# LCDTFT_FPC40P_SPI.net
KiCad netlist of a schematic drawn in Altium Designer
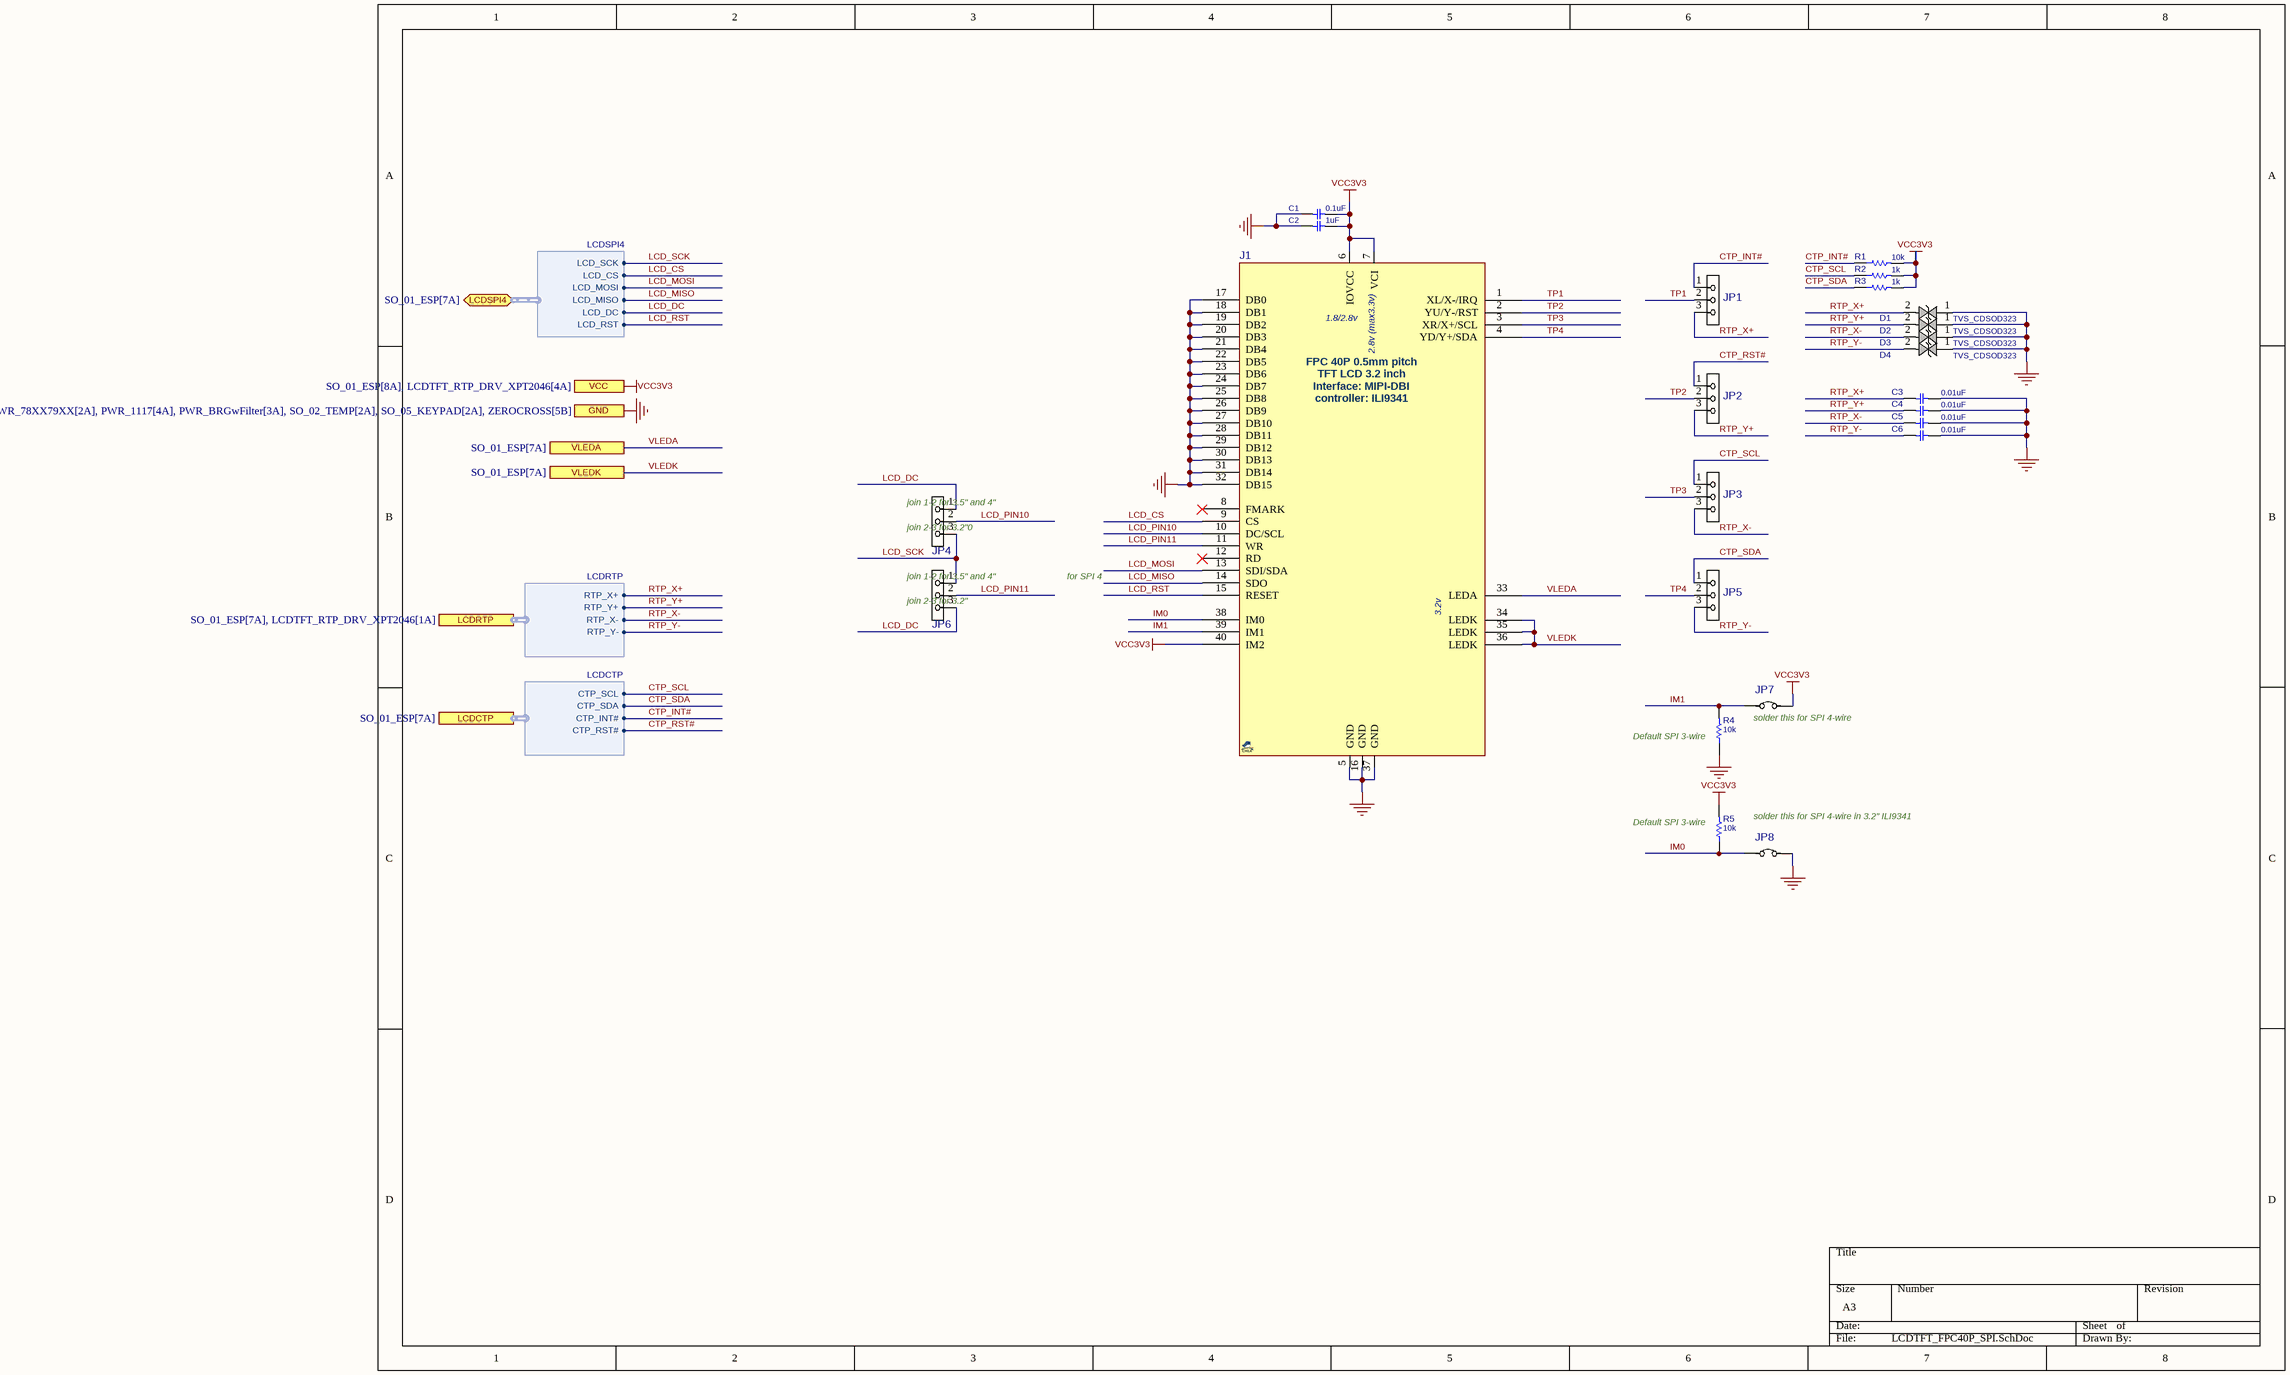
[diagram p0: LCDTFT_FPC40P_SPI.SchDoc]

(export (version "E")
  (design (tool "Eeschema 10.0.6"))
  (components
    (comp (ref "C1")
      (value "0.1uF")
      (footprint "C0402")
      (description "CAP, MLCC")
      (fields (field (name "MANF_P#") "GRM155R71H104KE14D") (field (name "MANF") "Murata"))
      (libsource (lib "passive_smd") (part "CAP_SMD_MLCC"))
    )
    (comp (ref "C2")
      (value "1uF")
      (footprint "C0402")
      (description "CAP, MLCC")
      (libsource (lib "passive_smd") (part "CAP_SMD_MLCC"))
    )
    (comp (ref "C3")
      (value "0.01uF")
      (footprint "C0402")
      (description "CAP, MLCC")
      (libsource (lib "passive_smd") (part "CAP_SMD_MLCC"))
    )
    (comp (ref "C4")
      (value "0.01uF")
      (footprint "C0402")
      (description "CAP, MLCC")
      (libsource (lib "passive_smd") (part "CAP_SMD_MLCC"))
    )
    (comp (ref "C5")
      (value "0.01uF")
      (footprint "C0402")
      (description "CAP, MLCC")
      (libsource (lib "passive_smd") (part "CAP_SMD_MLCC"))
    )
    (comp (ref "C6")
      (value "0.01uF")
      (footprint "C0402")
      (description "CAP, MLCC")
      (libsource (lib "passive_smd") (part "CAP_SMD_MLCC"))
    )
    (comp (ref "D1")
      (value "TVS_CDSOD323")
      (footprint "D0805")
      (description "TVS, ESD PROTECT, Bidirectional")
      (fields (field (name "MANF_P#") "CDSOD323-T12C") (field (name "MANF") "Bourns"))
      (libsource (lib "protect_tvs_esd_fuse") (part "TVS_CDSOD323"))
    )
    (comp (ref "D2")
      (value "TVS_CDSOD323")
      (footprint "D0805")
      (description "TVS, ESD PROTECT, Bidirectional")
      (fields (field (name "MANF_P#") "CDSOD323-T12C") (field (name "MANF") "Bourns"))
      (libsource (lib "protect_tvs_esd_fuse") (part "TVS_CDSOD323"))
    )
    (comp (ref "D3")
      (value "TVS_CDSOD323")
      (footprint "D0805")
      (description "TVS, ESD PROTECT, Bidirectional")
      (fields (field (name "MANF_P#") "CDSOD323-T12C") (field (name "MANF") "Bourns"))
      (libsource (lib "protect_tvs_esd_fuse") (part "TVS_CDSOD323"))
    )
    (comp (ref "D4")
      (value "TVS_CDSOD323")
      (footprint "D0805")
      (description "TVS, ESD PROTECT, Bidirectional")
      (fields (field (name "MANF_P#") "CDSOD323-T12C") (field (name "MANF") "Bourns"))
      (libsource (lib "protect_tvs_esd_fuse") (part "TVS_CDSOD323"))
    )
    (comp (ref "J1")
      (value "FPC50_40")
      (footprint "FPC50_40T")
      (description "LCD TFT Color, FPC40P, 3.2\" with touch")
      (fields (field (name "MANF") "Hirose") (field (name "MANF_P#") "FH12A-40S-0.5SH"))
      (libsource (lib "lcdtft") (part "LCDTFT_DBI_FPC40P_3.2INCH"))
    )
    (comp (ref "JP1")
      (value "JMPHDR3PIN")
      (footprint "JP_3_60W")
      (description "JUMPER, HEADER 3PIN")
      (fields (field (name "MANF") "MANF") (field (name "MANF_P#") "MANF_P#"))
      (libsource (lib "") (part "JUMPER_SOLDER_3P_1"))
    )
    (comp (ref "JP2")
      (value "JMPHDR3PIN")
      (footprint "JP_3_60W")
      (description "JUMPER, HEADER 3PIN")
      (fields (field (name "MANF") "MANF") (field (name "MANF_P#") "MANF_P#"))
      (libsource (lib "") (part "JUMPER_SOLDER_3P_1"))
    )
    (comp (ref "JP3")
      (value "JMPHDR3PIN")
      (footprint "JP_3_60W")
      (description "JUMPER, HEADER 3PIN")
      (fields (field (name "MANF") "MANF") (field (name "MANF_P#") "MANF_P#"))
      (libsource (lib "") (part "JUMPER_SOLDER_3P_1"))
    )
    (comp (ref "JP4")
      (value "JMPHDR3PIN")
      (footprint "JP_3_60W")
      (description "JUMPER, HEADER 3PIN")
      (fields (field (name "MANF") "MANF") (field (name "MANF_P#") "MANF_P#"))
      (libsource (lib "test-tp_jumper") (part "JUMPER_SOLDER_3P"))
    )
    (comp (ref "JP5")
      (value "JMPHDR3PIN")
      (footprint "JP_3_60W")
      (description "JUMPER, HEADER 3PIN")
      (fields (field (name "MANF") "MANF") (field (name "MANF_P#") "MANF_P#"))
      (libsource (lib "") (part "JUMPER_SOLDER_3P_1"))
    )
    (comp (ref "JP6")
      (value "JMPHDR3PIN")
      (footprint "JP_3_60W")
      (description "JUMPER, HEADER 3PIN")
      (fields (field (name "MANF") "MANF") (field (name "MANF_P#") "MANF_P#"))
      (libsource (lib "test-tp_jumper") (part "JUMPER_SOLDER_3P"))
    )
    (comp (ref "JP7")
      (value "JMPSOLDER")
      (footprint "JP_60X100")
      (description "JUMPER, HEADER 2PIN")
      (fields (field (name "MANF") "MANF") (field (name "MANF_P#") "MANF_P#"))
      (libsource (lib "test-tp_jumper") (part "JUMPER_SOLDER"))
    )
    (comp (ref "JP8")
      (value "JMPSOLDER")
      (footprint "JP_60X100")
      (description "JUMPER, HEADER 2PIN")
      (fields (field (name "MANF") "MANF") (field (name "MANF_P#") "MANF_P#"))
      (libsource (lib "test-tp_jumper") (part "JUMPER_SOLDER"))
    )
    (comp (ref "R1")
      (value "10k")
      (footprint "R0402")
      (description "RESISTOR, SMD")
      (libsource (lib "passive_res_smd") (part "RES_SMD"))
    )
    (comp (ref "R2")
      (value "1k")
      (footprint "R0402")
      (description "RESISTOR, SMD")
      (libsource (lib "passive_res_smd") (part "RES_SMD"))
    )
    (comp (ref "R3")
      (value "1k")
      (footprint "R0402")
      (description "RESISTOR, SMD")
      (libsource (lib "passive_res_smd") (part "RES_SMD"))
    )
    (comp (ref "R4")
      (value "10k")
      (footprint "R0402")
      (description "RESISTOR, SMD")
      (libsource (lib "passive_res_smd") (part "RES_SMD"))
    )
    (comp (ref "R5")
      (value "10k")
      (footprint "R0402")
      (description "RESISTOR, SMD")
      (libsource (lib "passive_res_smd") (part "RES_SMD"))
    )
  )
  (nets
    (net (code "4") (name "/CTP_INT#") (class "Default")
      (node (ref "JP1") (pin "1") (pinfunction "1_1") (pintype "passive"))
      (node (ref "R1") (pin "1") (pinfunction "1_1") (pintype "passive"))
    )
    (net (code "5") (name "/CTP_RST#") (class "Default")
      (node (ref "JP2") (pin "1") (pinfunction "1_1") (pintype "passive"))
    )
    (net (code "6") (name "/CTP_SCL") (class "Default")
      (node (ref "JP3") (pin "1") (pinfunction "1_1") (pintype "passive"))
      (node (ref "R2") (pin "1") (pinfunction "1_1") (pintype "passive"))
    )
    (net (code "7") (name "/CTP_SDA") (class "Default")
      (node (ref "JP5") (pin "1") (pinfunction "1_1") (pintype "passive"))
      (node (ref "R3") (pin "1") (pinfunction "1_1") (pintype "passive"))
    )
    (net (code "8") (name "/IM0") (class "Default")
      (node (ref "J1") (pin "38") (pinfunction "IM0_38") (pintype "passive"))
      (node (ref "JP8") (pin "1") (pinfunction "1_1") (pintype "passive"))
      (node (ref "R5") (pin "1") (pinfunction "1_1") (pintype "passive"))
    )
    (net (code "9") (name "/IM1") (class "Default")
      (node (ref "J1") (pin "39") (pinfunction "IM1_39") (pintype "passive"))
      (node (ref "JP7") (pin "1") (pinfunction "1_1") (pintype "passive"))
      (node (ref "R4") (pin "2") (pinfunction "2_2") (pintype "passive"))
    )
    (net (code "10") (name "/LCD_CS") (class "Default")
      (node (ref "J1") (pin "9") (pinfunction "CS_9") (pintype "passive"))
    )
    (net (code "11") (name "/LCD_DC") (class "Default")
      (node (ref "JP4") (pin "1") (pinfunction "1_1") (pintype "passive"))
      (node (ref "JP6") (pin "3") (pinfunction "3_3") (pintype "passive"))
    )
    (net (code "12") (name "/LCD_MISO") (class "Default")
      (node (ref "J1") (pin "14") (pinfunction "SDO_14") (pintype "passive"))
    )
    (net (code "13") (name "/LCD_MOSI") (class "Default")
      (node (ref "J1") (pin "13") (pinfunction "SDI/SDA_13") (pintype "passive"))
    )
    (net (code "14") (name "/LCD_PIN10") (class "Default")
      (node (ref "J1") (pin "10") (pinfunction "DC/SCL_10") (pintype "passive"))
      (node (ref "JP4") (pin "2") (pinfunction "2_2") (pintype "passive"))
    )
    (net (code "15") (name "/LCD_PIN11") (class "Default")
      (node (ref "J1") (pin "11") (pinfunction "WR_11") (pintype "passive"))
      (node (ref "JP6") (pin "2") (pinfunction "2_2") (pintype "passive"))
    )
    (net (code "16") (name "/LCD_RST") (class "Default")
      (node (ref "J1") (pin "15") (pinfunction "RESET_15") (pintype "passive"))
    )
    (net (code "17") (name "/LCD_SCK") (class "Default")
      (node (ref "JP4") (pin "3") (pinfunction "3_3") (pintype "passive"))
      (node (ref "JP6") (pin "1") (pinfunction "1_1") (pintype "passive"))
    )
    (net (code "18") (name "/RTP_X+") (class "Default")
      (node (ref "C3") (pin "2") (pinfunction "2_2") (pintype "passive"))
      (node (ref "D1") (pin "2") (pinfunction "2_2") (pintype "passive"))
      (node (ref "JP1") (pin "3") (pinfunction "3_3") (pintype "passive"))
    )
    (net (code "19") (name "/RTP_X-") (class "Default")
      (node (ref "C5") (pin "2") (pinfunction "2_2") (pintype "passive"))
      (node (ref "D3") (pin "2") (pinfunction "2_2") (pintype "passive"))
      (node (ref "JP3") (pin "3") (pinfunction "3_3") (pintype "passive"))
    )
    (net (code "20") (name "/RTP_Y+") (class "Default")
      (node (ref "C4") (pin "2") (pinfunction "2_2") (pintype "passive"))
      (node (ref "D2") (pin "2") (pinfunction "2_2") (pintype "passive"))
      (node (ref "JP2") (pin "3") (pinfunction "3_3") (pintype "passive"))
    )
    (net (code "21") (name "/RTP_Y-") (class "Default")
      (node (ref "C6") (pin "2") (pinfunction "2_2") (pintype "passive"))
      (node (ref "D4") (pin "2") (pinfunction "2_2") (pintype "passive"))
      (node (ref "JP5") (pin "3") (pinfunction "3_3") (pintype "passive"))
    )
    (net (code "22") (name "/TP1") (class "Default")
      (node (ref "J1") (pin "1") (pinfunction "XL/X-/IRQ_1") (pintype "passive"))
      (node (ref "JP1") (pin "2") (pinfunction "2_2") (pintype "passive"))
    )
    (net (code "23") (name "/TP2") (class "Default")
      (node (ref "J1") (pin "2") (pinfunction "YU/Y-/RST_2") (pintype "passive"))
      (node (ref "JP2") (pin "2") (pinfunction "2_2") (pintype "passive"))
    )
    (net (code "24") (name "/TP3") (class "Default")
      (node (ref "J1") (pin "3") (pinfunction "XR/X+/SCL_3") (pintype "passive"))
      (node (ref "JP3") (pin "2") (pinfunction "2_2") (pintype "passive"))
    )
    (net (code "25") (name "/TP4") (class "Default")
      (node (ref "J1") (pin "4") (pinfunction "YD/Y+/SDA_4") (pintype "passive"))
      (node (ref "JP5") (pin "2") (pinfunction "2_2") (pintype "passive"))
    )
    (net (code "26") (name "/VLEDA") (class "Default")
      (node (ref "J1") (pin "33") (pinfunction "LEDA_33") (pintype "passive"))
    )
    (net (code "27") (name "/VLEDK") (class "Default")
      (node (ref "J1") (pin "34") (pinfunction "LEDK_34") (pintype "passive"))
      (node (ref "J1") (pin "35") (pinfunction "LEDK_35") (pintype "passive"))
      (node (ref "J1") (pin "36") (pinfunction "LEDK_36") (pintype "passive"))
    )
    (net (code "31") (name "GND") (class "Default")
      (node (ref "C1") (pin "2") (pinfunction "2_2") (pintype "passive"))
      (node (ref "C2") (pin "2") (pinfunction "2_2") (pintype "passive"))
      (node (ref "C3") (pin "1") (pinfunction "1_1") (pintype "passive"))
      (node (ref "C4") (pin "1") (pinfunction "1_1") (pintype "passive"))
      (node (ref "C5") (pin "1") (pinfunction "1_1") (pintype "passive"))
      (node (ref "C6") (pin "1") (pinfunction "1_1") (pintype "passive"))
      (node (ref "D1") (pin "1") (pinfunction "1_1") (pintype "passive"))
      (node (ref "D2") (pin "1") (pinfunction "1_1") (pintype "passive"))
      (node (ref "D3") (pin "1") (pinfunction "1_1") (pintype "passive"))
      (node (ref "D4") (pin "1") (pinfunction "1_1") (pintype "passive"))
      (node (ref "J1") (pin "16") (pinfunction "GND_16") (pintype "passive"))
      (node (ref "J1") (pin "17") (pinfunction "DB0_17") (pintype "passive"))
      (node (ref "J1") (pin "18") (pinfunction "DB1_18") (pintype "passive"))
      (node (ref "J1") (pin "19") (pinfunction "DB2_19") (pintype "passive"))
      (node (ref "J1") (pin "20") (pinfunction "DB3_20") (pintype "passive"))
      (node (ref "J1") (pin "21") (pinfunction "DB4_21") (pintype "passive"))
      (node (ref "J1") (pin "22") (pinfunction "DB5_22") (pintype "passive"))
      (node (ref "J1") (pin "23") (pinfunction "DB6_23") (pintype "passive"))
      (node (ref "J1") (pin "24") (pinfunction "DB7_24") (pintype "passive"))
      (node (ref "J1") (pin "25") (pinfunction "DB8_25") (pintype "passive"))
      (node (ref "J1") (pin "26") (pinfunction "DB9_26") (pintype "passive"))
      (node (ref "J1") (pin "27") (pinfunction "DB10_27") (pintype "passive"))
      (node (ref "J1") (pin "28") (pinfunction "DB11_28") (pintype "passive"))
      (node (ref "J1") (pin "29") (pinfunction "DB12_29") (pintype "passive"))
      (node (ref "J1") (pin "30") (pinfunction "DB13_30") (pintype "passive"))
      (node (ref "J1") (pin "31") (pinfunction "DB14_31") (pintype "passive"))
      (node (ref "J1") (pin "32") (pinfunction "DB15_32") (pintype "passive"))
      (node (ref "J1") (pin "37") (pinfunction "GND_37") (pintype "passive"))
      (node (ref "J1") (pin "5") (pinfunction "GND_5") (pintype "passive"))
      (node (ref "JP8") (pin "2") (pinfunction "2_2") (pintype "passive"))
      (node (ref "R4") (pin "1") (pinfunction "1_1") (pintype "passive"))
    )
    (net (code "32") (name "VCC3V3") (class "Default")
      (node (ref "C1") (pin "1") (pinfunction "1_1") (pintype "passive"))
      (node (ref "C2") (pin "1") (pinfunction "1_1") (pintype "passive"))
      (node (ref "J1") (pin "40") (pinfunction "IM2_40") (pintype "passive"))
      (node (ref "J1") (pin "6") (pinfunction "IOVCC_6") (pintype "passive"))
      (node (ref "J1") (pin "7") (pinfunction "VCI_7") (pintype "passive"))
      (node (ref "JP7") (pin "2") (pinfunction "2_2") (pintype "passive"))
      (node (ref "R1") (pin "2") (pinfunction "2_2") (pintype "passive"))
      (node (ref "R2") (pin "2") (pinfunction "2_2") (pintype "passive"))
      (node (ref "R3") (pin "2") (pinfunction "2_2") (pintype "passive"))
      (node (ref "R5") (pin "2") (pinfunction "2_2") (pintype "passive"))
    )
    (net (code "33") (name "unconnected-(J1-FMARK-Pad8)") (class "Default")
      (node (ref "J1") (pin "8") (pinfunction "FMARK_8") (pintype "passive+no_connect"))
    )
    (net (code "34") (name "unconnected-(J1-RD-Pad12)") (class "Default")
      (node (ref "J1") (pin "12") (pinfunction "RD_12") (pintype "passive+no_connect"))
    )
  )
)
